# xmas.net
KiCad netlist of a schematic drawn in EAGLE
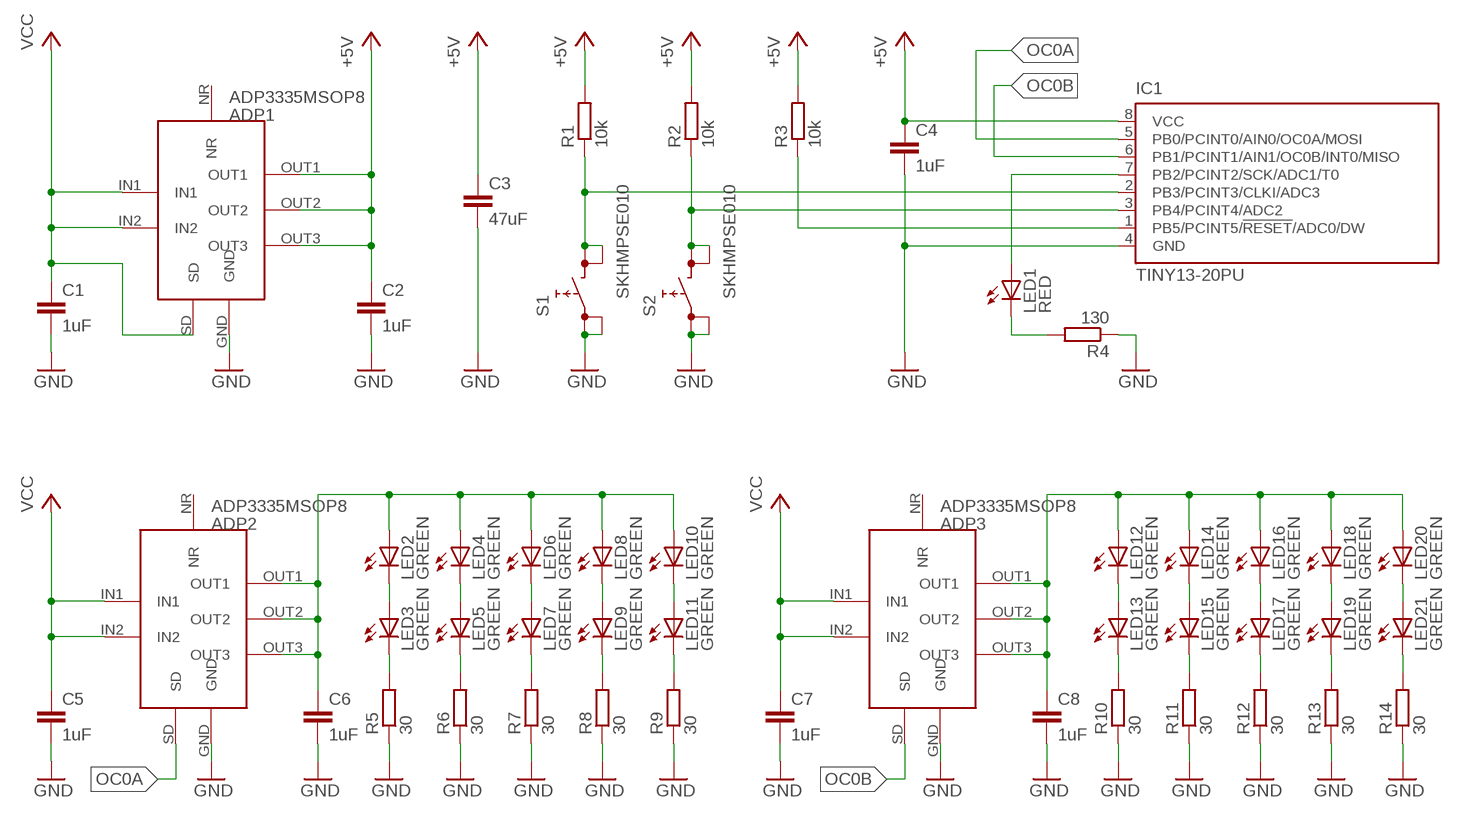
[diagram p0: schematic, sheet 1]

(export (version "E")
  (design (tool "Eeschema 10.0.6"))
  (components
    (comp (ref "ADP1")
      (value "ADP3335MSOP8")
      (footprint "eagle-import:MSOP8")
      (libsource (lib "eagle-import") (part "ADP3335MSOP8"))
    )
    (comp (ref "ADP2")
      (value "ADP3335MSOP8")
      (footprint "eagle-import:MSOP8")
      (libsource (lib "eagle-import") (part "ADP3335MSOP8"))
    )
    (comp (ref "ADP3")
      (value "ADP3335MSOP8")
      (footprint "eagle-import:MSOP8")
      (libsource (lib "eagle-import") (part "ADP3335MSOP8"))
    )
    (comp (ref "C1")
      (value "1uF")
      (footprint "eagle-import:C1206")
      (libsource (lib "eagle-import") (part "C-EUC1206"))
    )
    (comp (ref "C2")
      (value "1uF")
      (footprint "eagle-import:C1206")
      (libsource (lib "eagle-import") (part "C-EUC1206"))
    )
    (comp (ref "C3")
      (value "47uF")
      (footprint "eagle-import:C075-032X103")
      (libsource (lib "eagle-import") (part "C-EU075-032X103"))
    )
    (comp (ref "C4")
      (value "1uF")
      (footprint "eagle-import:C1206")
      (libsource (lib "eagle-import") (part "C-EUC1206"))
    )
    (comp (ref "C5")
      (value "1uF")
      (footprint "eagle-import:C1206")
      (libsource (lib "eagle-import") (part "C-EUC1206"))
    )
    (comp (ref "C6")
      (value "1uF")
      (footprint "eagle-import:C1206")
      (libsource (lib "eagle-import") (part "C-EUC1206"))
    )
    (comp (ref "C7")
      (value "1uF")
      (footprint "eagle-import:C1206")
      (libsource (lib "eagle-import") (part "C-EUC1206"))
    )
    (comp (ref "C8")
      (value "1uF")
      (footprint "eagle-import:C1206")
      (libsource (lib "eagle-import") (part "C-EUC1206"))
    )
    (comp (ref "IC1")
      (value "TINY13-20PU")
      (footprint "eagle-import:DIL08")
      (fields (field (name "MPN") "ATTINY13-20PU"))
      (libsource (lib "eagle-import") (part "TINY13PU-20"))
    )
    (comp (ref "LED1")
      (value "RED")
      (footprint "eagle-import:SMARTLED-TTW")
      (libsource (lib "eagle-import") (part "LED"))
    )
    (comp (ref "LED2")
      (value "GREEN")
      (footprint "eagle-import:SMARTLED-TTW")
      (libsource (lib "eagle-import") (part "LED"))
    )
    (comp (ref "LED3")
      (value "GREEN")
      (footprint "eagle-import:SMARTLED-TTW")
      (libsource (lib "eagle-import") (part "LED"))
    )
    (comp (ref "LED4")
      (value "GREEN")
      (footprint "eagle-import:SMARTLED-TTW")
      (libsource (lib "eagle-import") (part "LED"))
    )
    (comp (ref "LED5")
      (value "GREEN")
      (footprint "eagle-import:SMARTLED-TTW")
      (libsource (lib "eagle-import") (part "LED"))
    )
    (comp (ref "LED6")
      (value "GREEN")
      (footprint "eagle-import:SMARTLED-TTW")
      (libsource (lib "eagle-import") (part "LED"))
    )
    (comp (ref "LED7")
      (value "GREEN")
      (footprint "eagle-import:SMARTLED-TTW")
      (libsource (lib "eagle-import") (part "LED"))
    )
    (comp (ref "LED8")
      (value "GREEN")
      (footprint "eagle-import:SMARTLED-TTW")
      (libsource (lib "eagle-import") (part "LED"))
    )
    (comp (ref "LED9")
      (value "GREEN")
      (footprint "eagle-import:SMARTLED-TTW")
      (libsource (lib "eagle-import") (part "LED"))
    )
    (comp (ref "LED10")
      (value "GREEN")
      (footprint "eagle-import:SMARTLED-TTW")
      (libsource (lib "eagle-import") (part "LED"))
    )
    (comp (ref "LED11")
      (value "GREEN")
      (footprint "eagle-import:SMARTLED-TTW")
      (libsource (lib "eagle-import") (part "LED"))
    )
    (comp (ref "LED12")
      (value "GREEN")
      (footprint "eagle-import:SMARTLED-TTW")
      (libsource (lib "eagle-import") (part "LED"))
    )
    (comp (ref "LED13")
      (value "GREEN")
      (footprint "eagle-import:SMARTLED-TTW")
      (libsource (lib "eagle-import") (part "LED"))
    )
    (comp (ref "LED14")
      (value "GREEN")
      (footprint "eagle-import:SMARTLED-TTW")
      (libsource (lib "eagle-import") (part "LED"))
    )
    (comp (ref "LED15")
      (value "GREEN")
      (footprint "eagle-import:SMARTLED-TTW")
      (libsource (lib "eagle-import") (part "LED"))
    )
    (comp (ref "LED16")
      (value "GREEN")
      (footprint "eagle-import:SMARTLED-TTW")
      (libsource (lib "eagle-import") (part "LED"))
    )
    (comp (ref "LED17")
      (value "GREEN")
      (footprint "eagle-import:SMARTLED-TTW")
      (libsource (lib "eagle-import") (part "LED"))
    )
    (comp (ref "LED18")
      (value "GREEN")
      (footprint "eagle-import:SMARTLED-TTW")
      (libsource (lib "eagle-import") (part "LED"))
    )
    (comp (ref "LED19")
      (value "GREEN")
      (footprint "eagle-import:SMARTLED-TTW")
      (libsource (lib "eagle-import") (part "LED"))
    )
    (comp (ref "LED20")
      (value "GREEN")
      (footprint "eagle-import:SMARTLED-TTW")
      (libsource (lib "eagle-import") (part "LED"))
    )
    (comp (ref "LED21")
      (value "GREEN")
      (footprint "eagle-import:SMARTLED-TTW")
      (libsource (lib "eagle-import") (part "LED"))
    )
    (comp (ref "R1")
      (value "10k")
      (footprint "eagle-import:R1206")
      (libsource (lib "eagle-import") (part "R-EU_R1206"))
    )
    (comp (ref "R2")
      (value "10k")
      (footprint "eagle-import:R1206")
      (libsource (lib "eagle-import") (part "R-EU_R1206"))
    )
    (comp (ref "R3")
      (value "10k")
      (footprint "eagle-import:R1206")
      (libsource (lib "eagle-import") (part "R-EU_R1206"))
    )
    (comp (ref "R4")
      (value "130")
      (footprint "eagle-import:0207_10")
      (libsource (lib "eagle-import") (part "R-EU_0207/10"))
    )
    (comp (ref "R5")
      (value "30")
      (footprint "eagle-import:R1206")
      (libsource (lib "eagle-import") (part "R-EU_R1206"))
    )
    (comp (ref "R6")
      (value "30")
      (footprint "eagle-import:R1206")
      (libsource (lib "eagle-import") (part "R-EU_R1206"))
    )
    (comp (ref "R7")
      (value "30")
      (footprint "eagle-import:R1206")
      (libsource (lib "eagle-import") (part "R-EU_R1206"))
    )
    (comp (ref "R8")
      (value "30")
      (footprint "eagle-import:R1206")
      (libsource (lib "eagle-import") (part "R-EU_R1206"))
    )
    (comp (ref "R9")
      (value "30")
      (footprint "eagle-import:R1206")
      (libsource (lib "eagle-import") (part "R-EU_R1206"))
    )
    (comp (ref "R10")
      (value "30")
      (footprint "eagle-import:R1206")
      (libsource (lib "eagle-import") (part "R-EU_R1206"))
    )
    (comp (ref "R11")
      (value "30")
      (footprint "eagle-import:R1206")
      (libsource (lib "eagle-import") (part "R-EU_R1206"))
    )
    (comp (ref "R12")
      (value "30")
      (footprint "eagle-import:R1206")
      (libsource (lib "eagle-import") (part "R-EU_R1206"))
    )
    (comp (ref "R13")
      (value "30")
      (footprint "eagle-import:R1206")
      (libsource (lib "eagle-import") (part "R-EU_R1206"))
    )
    (comp (ref "R14")
      (value "30")
      (footprint "eagle-import:R1206")
      (libsource (lib "eagle-import") (part "R-EU_R1206"))
    )
    (comp (ref "S1")
      (value "SKHMPSE010")
      (footprint "eagle-import:SKHMPXE010")
      (libsource (lib "eagle-import") (part "SKHMPE010S"))
    )
    (comp (ref "S2")
      (value "SKHMPSE010")
      (footprint "eagle-import:SKHMPXE010")
      (libsource (lib "eagle-import") (part "SKHMPE010S"))
    )
  )
  (nets
    (net (code "1") (name "+5V") (class "Default")
      (node (ref "ADP1") (pin "OUT1") (pinfunction "OUT1_OUT1") (pintype "bidirectional"))
      (node (ref "ADP1") (pin "OUT2") (pinfunction "OUT2_OUT2") (pintype "bidirectional"))
      (node (ref "ADP1") (pin "OUT3") (pinfunction "OUT3_OUT3") (pintype "bidirectional"))
      (node (ref "C2") (pin "1") (pinfunction "1_1") (pintype "passive"))
      (node (ref "C3") (pin "1") (pinfunction "1_1") (pintype "passive"))
      (node (ref "C4") (pin "1") (pinfunction "1_1") (pintype "passive"))
      (node (ref "IC1") (pin "8") (pinfunction "VCC_8") (pintype "power_in"))
      (node (ref "R1") (pin "2") (pinfunction "2_2") (pintype "passive"))
      (node (ref "R2") (pin "2") (pinfunction "2_2") (pintype "passive"))
      (node (ref "R3") (pin "2") (pinfunction "2_2") (pintype "passive"))
    )
    (net (code "2") (name "GND") (class "Default")
      (node (ref "ADP1") (pin "GND") (pinfunction "GND_GND") (pintype "bidirectional"))
      (node (ref "ADP2") (pin "GND") (pinfunction "GND_GND") (pintype "bidirectional"))
      (node (ref "ADP3") (pin "GND") (pinfunction "GND_GND") (pintype "bidirectional"))
      (node (ref "C1") (pin "2") (pinfunction "2_2") (pintype "passive"))
      (node (ref "C2") (pin "2") (pinfunction "2_2") (pintype "passive"))
      (node (ref "C3") (pin "2") (pinfunction "2_2") (pintype "passive"))
      (node (ref "C4") (pin "2") (pinfunction "2_2") (pintype "passive"))
      (node (ref "C5") (pin "2") (pinfunction "2_2") (pintype "passive"))
      (node (ref "C6") (pin "2") (pinfunction "2_2") (pintype "passive"))
      (node (ref "C7") (pin "2") (pinfunction "2_2") (pintype "passive"))
      (node (ref "C8") (pin "2") (pinfunction "2_2") (pintype "passive"))
      (node (ref "IC1") (pin "4") (pinfunction "GND_4") (pintype "power_in"))
      (node (ref "R10") (pin "1") (pinfunction "1_1") (pintype "passive"))
      (node (ref "R11") (pin "1") (pinfunction "1_1") (pintype "passive"))
      (node (ref "R12") (pin "1") (pinfunction "1_1") (pintype "passive"))
      (node (ref "R13") (pin "1") (pinfunction "1_1") (pintype "passive"))
      (node (ref "R14") (pin "1") (pinfunction "1_1") (pintype "passive"))
      (node (ref "R4") (pin "1") (pinfunction "1_1") (pintype "passive"))
      (node (ref "R5") (pin "1") (pinfunction "1_1") (pintype "passive"))
      (node (ref "R6") (pin "1") (pinfunction "1_1") (pintype "passive"))
      (node (ref "R7") (pin "1") (pinfunction "1_1") (pintype "passive"))
      (node (ref "R8") (pin "1") (pinfunction "1_1") (pintype "passive"))
      (node (ref "R9") (pin "1") (pinfunction "1_1") (pintype "passive"))
      (node (ref "S1") (pin "1") (pinfunction "1.1_1") (pintype "passive"))
      (node (ref "S1") (pin "2") (pinfunction "1.2_2") (pintype "passive"))
      (node (ref "S2") (pin "1") (pinfunction "1.1_1") (pintype "passive"))
      (node (ref "S2") (pin "2") (pinfunction "1.2_2") (pintype "passive"))
    )
    (net (code "3") (name "Net-(IC1-PB2{slash}PCINT2{slash}SCK{slash}ADC1{slash}T0)") (class "Default")
      (node (ref "IC1") (pin "7") (pinfunction "PB2/PCINT2/SCK/ADC1/T0_7") (pintype "bidirectional"))
      (node (ref "LED1") (pin "A@1") (pinfunction "A_A@1") (pintype "passive"))
    )
    (net (code "4") (name "Net-(IC1-PB3{slash}PCINT3{slash}CLKI{slash}ADC3)") (class "Default")
      (node (ref "IC1") (pin "2") (pinfunction "PB3/PCINT3/CLKI/ADC3_2") (pintype "bidirectional"))
      (node (ref "R1") (pin "1") (pinfunction "1_1") (pintype "passive"))
      (node (ref "S1") (pin "3") (pinfunction "2.1_3") (pintype "passive"))
      (node (ref "S1") (pin "4") (pinfunction "2.2_4") (pintype "passive"))
    )
    (net (code "5") (name "Net-(IC1-PB4{slash}PCINT4{slash}ADC2)") (class "Default")
      (node (ref "IC1") (pin "3") (pinfunction "PB4/PCINT4/ADC2_3") (pintype "bidirectional"))
      (node (ref "R2") (pin "1") (pinfunction "1_1") (pintype "passive"))
      (node (ref "S2") (pin "3") (pinfunction "2.1_3") (pintype "passive"))
      (node (ref "S2") (pin "4") (pinfunction "2.2_4") (pintype "passive"))
    )
    (net (code "6") (name "Net-(IC1-PB5{slash}PCINT5{slash}~{RESET}{slash}ADC0{slash}DW)") (class "Default")
      (node (ref "IC1") (pin "1") (pinfunction "PB5/PCINT5/~{RESET}/ADC0/DW_1") (pintype "bidirectional"))
      (node (ref "R3") (pin "1") (pinfunction "1_1") (pintype "passive"))
    )
    (net (code "7") (name "Net-(LED1-C)") (class "Default")
      (node (ref "LED1") (pin "C@1") (pinfunction "C_C@1") (pintype "passive"))
      (node (ref "R4") (pin "2") (pinfunction "2_2") (pintype "passive"))
    )
    (net (code "8") (name "Net-(LED2-C)") (class "Default")
      (node (ref "LED2") (pin "C@1") (pinfunction "C_C@1") (pintype "passive"))
      (node (ref "LED3") (pin "A@1") (pinfunction "A_A@1") (pintype "passive"))
    )
    (net (code "9") (name "Net-(LED3-C)") (class "Default")
      (node (ref "LED3") (pin "C@1") (pinfunction "C_C@1") (pintype "passive"))
      (node (ref "R5") (pin "2") (pinfunction "2_2") (pintype "passive"))
    )
    (net (code "10") (name "Net-(LED4-C)") (class "Default")
      (node (ref "LED4") (pin "C@1") (pinfunction "C_C@1") (pintype "passive"))
      (node (ref "LED5") (pin "A@1") (pinfunction "A_A@1") (pintype "passive"))
    )
    (net (code "11") (name "Net-(LED5-C)") (class "Default")
      (node (ref "LED5") (pin "C@1") (pinfunction "C_C@1") (pintype "passive"))
      (node (ref "R6") (pin "2") (pinfunction "2_2") (pintype "passive"))
    )
    (net (code "12") (name "Net-(LED6-C)") (class "Default")
      (node (ref "LED6") (pin "C@1") (pinfunction "C_C@1") (pintype "passive"))
      (node (ref "LED7") (pin "A@1") (pinfunction "A_A@1") (pintype "passive"))
    )
    (net (code "13") (name "Net-(LED7-C)") (class "Default")
      (node (ref "LED7") (pin "C@1") (pinfunction "C_C@1") (pintype "passive"))
      (node (ref "R7") (pin "2") (pinfunction "2_2") (pintype "passive"))
    )
    (net (code "14") (name "Net-(LED8-C)") (class "Default")
      (node (ref "LED8") (pin "C@1") (pinfunction "C_C@1") (pintype "passive"))
      (node (ref "LED9") (pin "A@1") (pinfunction "A_A@1") (pintype "passive"))
    )
    (net (code "15") (name "Net-(LED9-C)") (class "Default")
      (node (ref "LED9") (pin "C@1") (pinfunction "C_C@1") (pintype "passive"))
      (node (ref "R8") (pin "2") (pinfunction "2_2") (pintype "passive"))
    )
    (net (code "16") (name "Net-(LED10-A)") (class "Default")
      (node (ref "ADP2") (pin "OUT1") (pinfunction "OUT1_OUT1") (pintype "bidirectional"))
      (node (ref "ADP2") (pin "OUT2") (pinfunction "OUT2_OUT2") (pintype "bidirectional"))
      (node (ref "ADP2") (pin "OUT3") (pinfunction "OUT3_OUT3") (pintype "bidirectional"))
      (node (ref "C6") (pin "1") (pinfunction "1_1") (pintype "passive"))
      (node (ref "LED10") (pin "A@1") (pinfunction "A_A@1") (pintype "passive"))
      (node (ref "LED2") (pin "A@1") (pinfunction "A_A@1") (pintype "passive"))
      (node (ref "LED4") (pin "A@1") (pinfunction "A_A@1") (pintype "passive"))
      (node (ref "LED6") (pin "A@1") (pinfunction "A_A@1") (pintype "passive"))
      (node (ref "LED8") (pin "A@1") (pinfunction "A_A@1") (pintype "passive"))
    )
    (net (code "17") (name "Net-(LED10-C)") (class "Default")
      (node (ref "LED10") (pin "C@1") (pinfunction "C_C@1") (pintype "passive"))
      (node (ref "LED11") (pin "A@1") (pinfunction "A_A@1") (pintype "passive"))
    )
    (net (code "18") (name "Net-(LED11-C)") (class "Default")
      (node (ref "LED11") (pin "C@1") (pinfunction "C_C@1") (pintype "passive"))
      (node (ref "R9") (pin "2") (pinfunction "2_2") (pintype "passive"))
    )
    (net (code "19") (name "Net-(LED12-A)") (class "Default")
      (node (ref "ADP3") (pin "OUT1") (pinfunction "OUT1_OUT1") (pintype "bidirectional"))
      (node (ref "ADP3") (pin "OUT2") (pinfunction "OUT2_OUT2") (pintype "bidirectional"))
      (node (ref "ADP3") (pin "OUT3") (pinfunction "OUT3_OUT3") (pintype "bidirectional"))
      (node (ref "C8") (pin "1") (pinfunction "1_1") (pintype "passive"))
      (node (ref "LED12") (pin "A@1") (pinfunction "A_A@1") (pintype "passive"))
      (node (ref "LED14") (pin "A@1") (pinfunction "A_A@1") (pintype "passive"))
      (node (ref "LED16") (pin "A@1") (pinfunction "A_A@1") (pintype "passive"))
      (node (ref "LED18") (pin "A@1") (pinfunction "A_A@1") (pintype "passive"))
      (node (ref "LED20") (pin "A@1") (pinfunction "A_A@1") (pintype "passive"))
    )
    (net (code "20") (name "Net-(LED12-C)") (class "Default")
      (node (ref "LED12") (pin "C@1") (pinfunction "C_C@1") (pintype "passive"))
      (node (ref "LED13") (pin "A@1") (pinfunction "A_A@1") (pintype "passive"))
    )
    (net (code "21") (name "Net-(LED13-C)") (class "Default")
      (node (ref "LED13") (pin "C@1") (pinfunction "C_C@1") (pintype "passive"))
      (node (ref "R10") (pin "2") (pinfunction "2_2") (pintype "passive"))
    )
    (net (code "22") (name "Net-(LED14-C)") (class "Default")
      (node (ref "LED14") (pin "C@1") (pinfunction "C_C@1") (pintype "passive"))
      (node (ref "LED15") (pin "A@1") (pinfunction "A_A@1") (pintype "passive"))
    )
    (net (code "23") (name "Net-(LED15-C)") (class "Default")
      (node (ref "LED15") (pin "C@1") (pinfunction "C_C@1") (pintype "passive"))
      (node (ref "R11") (pin "2") (pinfunction "2_2") (pintype "passive"))
    )
    (net (code "24") (name "Net-(LED16-C)") (class "Default")
      (node (ref "LED16") (pin "C@1") (pinfunction "C_C@1") (pintype "passive"))
      (node (ref "LED17") (pin "A@1") (pinfunction "A_A@1") (pintype "passive"))
    )
    (net (code "25") (name "Net-(LED17-C)") (class "Default")
      (node (ref "LED17") (pin "C@1") (pinfunction "C_C@1") (pintype "passive"))
      (node (ref "R12") (pin "2") (pinfunction "2_2") (pintype "passive"))
    )
    (net (code "26") (name "Net-(LED18-C)") (class "Default")
      (node (ref "LED18") (pin "C@1") (pinfunction "C_C@1") (pintype "passive"))
      (node (ref "LED19") (pin "A@1") (pinfunction "A_A@1") (pintype "passive"))
    )
    (net (code "27") (name "Net-(LED19-C)") (class "Default")
      (node (ref "LED19") (pin "C@1") (pinfunction "C_C@1") (pintype "passive"))
      (node (ref "R13") (pin "2") (pinfunction "2_2") (pintype "passive"))
    )
    (net (code "28") (name "Net-(LED20-C)") (class "Default")
      (node (ref "LED20") (pin "C@1") (pinfunction "C_C@1") (pintype "passive"))
      (node (ref "LED21") (pin "A@1") (pinfunction "A_A@1") (pintype "passive"))
    )
    (net (code "29") (name "Net-(LED21-C)") (class "Default")
      (node (ref "LED21") (pin "C@1") (pinfunction "C_C@1") (pintype "passive"))
      (node (ref "R14") (pin "2") (pinfunction "2_2") (pintype "passive"))
    )
    (net (code "30") (name "OC0A") (class "Default")
      (node (ref "ADP2") (pin "SD") (pinfunction "SD_SD") (pintype "bidirectional"))
      (node (ref "IC1") (pin "5") (pinfunction "PB0/PCINT0/AIN0/OC0A/MOSI_5") (pintype "bidirectional"))
    )
    (net (code "31") (name "OC0B") (class "Default")
      (node (ref "ADP3") (pin "SD") (pinfunction "SD_SD") (pintype "bidirectional"))
      (node (ref "IC1") (pin "6") (pinfunction "PB1/PCINT1/AIN1/OC0B/INT0/MISO_6") (pintype "bidirectional"))
    )
    (net (code "32") (name "VCC") (class "Default")
      (node (ref "ADP1") (pin "IN1") (pinfunction "IN1_IN1") (pintype "bidirectional"))
      (node (ref "ADP1") (pin "IN2") (pinfunction "IN2_IN2") (pintype "bidirectional"))
      (node (ref "ADP1") (pin "SD") (pinfunction "SD_SD") (pintype "bidirectional"))
      (node (ref "ADP2") (pin "IN1") (pinfunction "IN1_IN1") (pintype "bidirectional"))
      (node (ref "ADP2") (pin "IN2") (pinfunction "IN2_IN2") (pintype "bidirectional"))
      (node (ref "ADP3") (pin "IN1") (pinfunction "IN1_IN1") (pintype "bidirectional"))
      (node (ref "ADP3") (pin "IN2") (pinfunction "IN2_IN2") (pintype "bidirectional"))
      (node (ref "C1") (pin "1") (pinfunction "1_1") (pintype "passive"))
      (node (ref "C5") (pin "1") (pinfunction "1_1") (pintype "passive"))
      (node (ref "C7") (pin "1") (pinfunction "1_1") (pintype "passive"))
    )
    (net (code "33") (name "unconnected-(ADP1-PadNR)") (class "Default")
      (node (ref "ADP1") (pin "NR") (pinfunction "NR_NR") (pintype "bidirectional"))
    )
    (net (code "34") (name "unconnected-(ADP2-PadNR)") (class "Default")
      (node (ref "ADP2") (pin "NR") (pinfunction "NR_NR") (pintype "bidirectional"))
    )
    (net (code "35") (name "unconnected-(ADP3-PadNR)") (class "Default")
      (node (ref "ADP3") (pin "NR") (pinfunction "NR_NR") (pintype "bidirectional"))
    )
  )
)
